# NGFF_B.net
KiCad netlist of a schematic drawn in Altium Designer
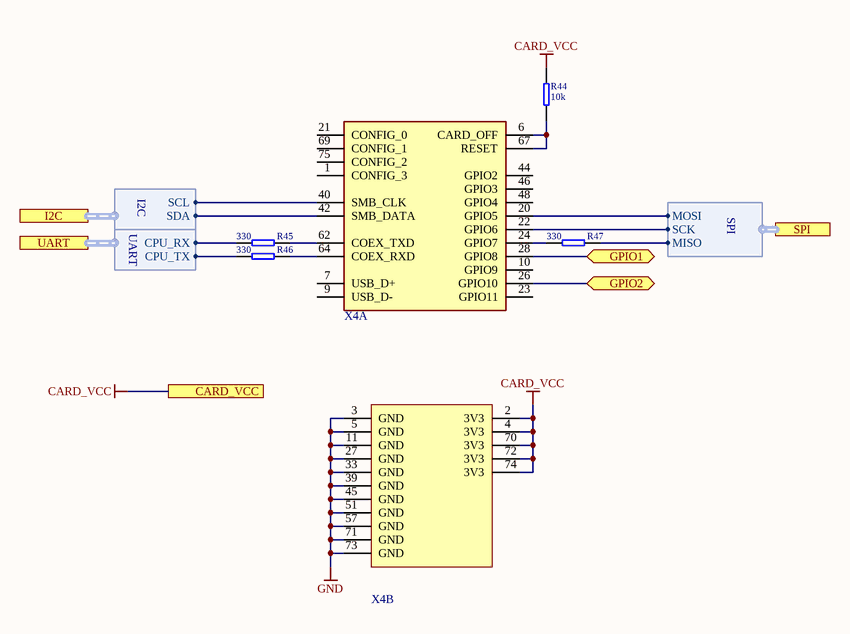
[diagram p0: NGFF_B.SchDoc]

(export (version "E")
  (design (tool "Eeschema 10.0.6"))
  (components
    (comp (ref "R44")
      (value "10k")
      (footprint "RES 0402")
      (description "Resistor")
      (fields (field (name "Comment") "RES 0402 10k"))
      (libsource (lib "!main") (part "!Resistor"))
    )
    (comp (ref "R45")
      (value "330")
      (footprint "RES 0402")
      (description "Resistor")
      (fields (field (name "Comment") "RES 0402 330"))
      (libsource (lib "!main") (part "!Resistor"))
    )
    (comp (ref "R46")
      (value "330")
      (footprint "RES 0402")
      (description "Resistor")
      (fields (field (name "Comment") "RES 0402 330"))
      (libsource (lib "!main") (part "!Resistor"))
    )
    (comp (ref "R47")
      (value "330")
      (footprint "RES 0402")
      (description "Resistor")
      (fields (field (name "Comment") "RES 0402 330"))
      (libsource (lib "!main") (part "!Resistor"))
    )
    (comp (ref "X4")
      (value "2199230-3")
      (footprint "NGFF_B3_30MM")
      (description "M.2 0.5PITCH 4.2H KEY B 15U'' AU")
      (libsource (lib "connectors") (part "NGFF_B"))
    )
  )
  (nets
    (net (code "4") (name "/CPU_RX") (class "Default")
      (node (ref "R45") (pin "1") (pinfunction "11_1") (pintype "passive"))
    )
    (net (code "5") (name "/CPU_TX") (class "Default")
      (node (ref "R46") (pin "1") (pinfunction "11_1") (pintype "passive"))
    )
    (net (code "6") (name "/GPIO1") (class "Default")
      (node (ref "X4") (pin "28") (pinfunction "GPIO8_28") (pintype "passive"))
    )
    (net (code "7") (name "/GPIO2") (class "Default")
      (node (ref "X4") (pin "26") (pinfunction "GPIO10_26") (pintype "passive"))
    )
    (net (code "8") (name "/MISO") (class "Default")
      (node (ref "R47") (pin "2") (pinfunction "12_2") (pintype "passive"))
    )
    (net (code "9") (name "/MOSI") (class "Default")
      (node (ref "X4") (pin "20") (pinfunction "GPIO5_20") (pintype "passive"))
    )
    (net (code "10") (name "/SCK") (class "Default")
      (node (ref "X4") (pin "22") (pinfunction "GPIO6_22") (pintype "passive"))
    )
    (net (code "11") (name "/SCL") (class "Default")
      (node (ref "X4") (pin "40") (pinfunction "SMB_CLK_40") (pintype "passive"))
    )
    (net (code "12") (name "/SDA") (class "Default")
      (node (ref "X4") (pin "42") (pinfunction "SMB_DATA_42") (pintype "passive"))
    )
    (net (code "16") (name "CARD_VCC") (class "Default")
      (node (ref "R44") (pin "2") (pinfunction "12_2") (pintype "passive"))
      (node (ref "X4") (pin "2") (pinfunction "3V3_2") (pintype "passive"))
      (node (ref "X4") (pin "4") (pinfunction "3V3_4") (pintype "passive"))
      (node (ref "X4") (pin "70") (pinfunction "3V3_70") (pintype "passive"))
      (node (ref "X4") (pin "72") (pinfunction "3V3_72") (pintype "passive"))
      (node (ref "X4") (pin "74") (pinfunction "3V3_74") (pintype "passive"))
    )
    (net (code "17") (name "GND") (class "Default")
      (node (ref "X4") (pin "11") (pinfunction "GND_11") (pintype "passive"))
      (node (ref "X4") (pin "27") (pinfunction "GND_27") (pintype "passive"))
      (node (ref "X4") (pin "3") (pinfunction "GND_3") (pintype "passive"))
      (node (ref "X4") (pin "33") (pinfunction "GND_33") (pintype "passive"))
      (node (ref "X4") (pin "39") (pinfunction "GND_39") (pintype "passive"))
      (node (ref "X4") (pin "45") (pinfunction "GND_45") (pintype "passive"))
      (node (ref "X4") (pin "5") (pinfunction "GND_5") (pintype "passive"))
      (node (ref "X4") (pin "51") (pinfunction "GND_51") (pintype "passive"))
      (node (ref "X4") (pin "57") (pinfunction "GND_57") (pintype "passive"))
      (node (ref "X4") (pin "71") (pinfunction "GND_71") (pintype "passive"))
      (node (ref "X4") (pin "73") (pinfunction "GND_73") (pintype "passive"))
    )
    (net (code "18") (name "Net-(R44-11)") (class "Default")
      (node (ref "R44") (pin "1") (pinfunction "11_1") (pintype "passive"))
      (node (ref "X4") (pin "6") (pinfunction "CARD_OFF_6") (pintype "passive"))
      (node (ref "X4") (pin "67") (pinfunction "RESET_67") (pintype "passive"))
    )
    (net (code "19") (name "Net-(R45-12)") (class "Default")
      (node (ref "R45") (pin "2") (pinfunction "12_2") (pintype "passive"))
      (node (ref "X4") (pin "62") (pinfunction "COEX_TXD_62") (pintype "passive"))
    )
    (net (code "20") (name "Net-(R46-12)") (class "Default")
      (node (ref "R46") (pin "2") (pinfunction "12_2") (pintype "passive"))
      (node (ref "X4") (pin "64") (pinfunction "COEX_RXD_64") (pintype "passive"))
    )
    (net (code "21") (name "Net-(R47-11)") (class "Default")
      (node (ref "R47") (pin "1") (pinfunction "11_1") (pintype "passive"))
      (node (ref "X4") (pin "24") (pinfunction "GPIO7_24") (pintype "passive"))
    )
    (net (code "22") (name "unconnected-(X4A-CONFIG_0-Pad21)") (class "Default")
      (node (ref "X4") (pin "21") (pinfunction "CONFIG_0_21") (pintype "passive"))
    )
    (net (code "23") (name "unconnected-(X4A-CONFIG_1-Pad69)") (class "Default")
      (node (ref "X4") (pin "69") (pinfunction "CONFIG_1_69") (pintype "passive"))
    )
    (net (code "24") (name "unconnected-(X4A-CONFIG_2-Pad75)") (class "Default")
      (node (ref "X4") (pin "75") (pinfunction "CONFIG_2_75") (pintype "passive"))
    )
    (net (code "25") (name "unconnected-(X4A-CONFIG_3-Pad1)") (class "Default")
      (node (ref "X4") (pin "1") (pinfunction "CONFIG_3_1") (pintype "passive"))
    )
    (net (code "26") (name "unconnected-(X4A-GPIO2-Pad44)") (class "Default")
      (node (ref "X4") (pin "44") (pinfunction "GPIO2_44") (pintype "passive"))
    )
    (net (code "27") (name "unconnected-(X4A-GPIO3-Pad46)") (class "Default")
      (node (ref "X4") (pin "46") (pinfunction "GPIO3_46") (pintype "passive"))
    )
    (net (code "28") (name "unconnected-(X4A-GPIO4-Pad48)") (class "Default")
      (node (ref "X4") (pin "48") (pinfunction "GPIO4_48") (pintype "passive"))
    )
    (net (code "29") (name "unconnected-(X4A-GPIO9-Pad10)") (class "Default")
      (node (ref "X4") (pin "10") (pinfunction "GPIO9_10") (pintype "passive"))
    )
    (net (code "30") (name "unconnected-(X4A-GPIO11-Pad23)") (class "Default")
      (node (ref "X4") (pin "23") (pinfunction "GPIO11_23") (pintype "passive"))
    )
    (net (code "31") (name "unconnected-(X4A-USB_D+-Pad7)") (class "Default")
      (node (ref "X4") (pin "7") (pinfunction "USB_D+_7") (pintype "passive"))
    )
    (net (code "32") (name "unconnected-(X4A-USB_D--Pad9)") (class "Default")
      (node (ref "X4") (pin "9") (pinfunction "USB_D-_9") (pintype "passive"))
    )
  )
)
